# 7_Temp.net
KiCad netlist of a schematic drawn in Altium Designer
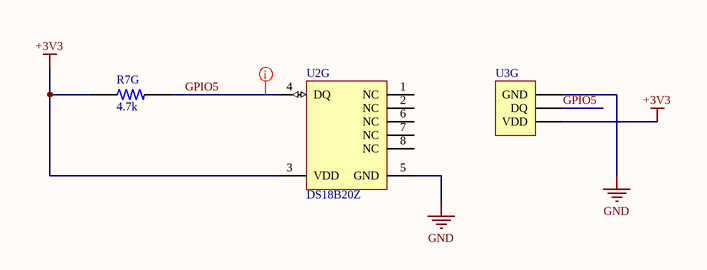
[diagram p0: 7_Temp.SchDoc]

(export (version "E")
  (design (tool "Eeschema 10.0.6"))
  (components
    (comp (ref "R7G")
      (value "4.7k")
      (footprint "R-0603")
      (description "0603")
      (fields (field (name "MP") "2-1623703-0") (field (name "TOLERANCE") "1%"))
      (libsource (lib "ESP-12F_WLED_IOT_LIPO") (part "R-0603"))
    )
    (comp (ref "U2G")
      (value "DS18B20Z")
      (footprint "MAXM-S8-2_N")
      (description "High-Precision 1-Wire Digital Thermometer, -55 to 125 degC, 8-Pin SOIC (S8-2)")
      (fields (field (name "GENERIC PART NUMBER") "DS18B20"))
      (libsource (lib "ESP-12F_WLED_IOT_LIPO") (part "DS18B20-S8-2"))
    )
    (comp (ref "U3G")
      (value "Header 3")
      (footprint "HDR1X3")
      (description "Header, 3-Pin")
      (fields (field (name "PUBLISHER") "Altium Limited"))
      (libsource (lib "ESP-12F_WLED_IOT_LIPO") (part "Header 3"))
    )
  )
  (nets
    (net (code "1") (name "+3V3") (class "Default")
      (node (ref "R7G") (pin "1") (pinfunction "1_1") (pintype "passive"))
      (node (ref "U2G") (pin "3") (pinfunction "VDD_3") (pintype "power_in"))
      (node (ref "U3G") (pin "3") (pinfunction "VDD_3") (pintype "passive"))
    )
    (net (code "2") (name "/GPIO5") (class "Default")
      (node (ref "R7G") (pin "2") (pinfunction "2_2") (pintype "passive"))
      (node (ref "U2G") (pin "4") (pinfunction "DQ_4") (pintype "bidirectional"))
      (node (ref "U3G") (pin "2") (pinfunction "DQ_2") (pintype "passive"))
    )
    (net (code "3") (name "GND") (class "Default")
      (node (ref "U2G") (pin "5") (pinfunction "GND_5") (pintype "power_in"))
      (node (ref "U3G") (pin "1") (pinfunction "GND_1") (pintype "passive"))
    )
    (net (code "4") (name "unconnected-(U2G-NC-Pad1)") (class "Default")
      (node (ref "U2G") (pin "1") (pinfunction "NC_1") (pintype "passive"))
    )
    (net (code "5") (name "unconnected-(U2G-NC-Pad2)") (class "Default")
      (node (ref "U2G") (pin "2") (pinfunction "NC_2") (pintype "passive"))
    )
    (net (code "6") (name "unconnected-(U2G-NC-Pad6)") (class "Default")
      (node (ref "U2G") (pin "6") (pinfunction "NC_6") (pintype "passive"))
    )
    (net (code "7") (name "unconnected-(U2G-NC-Pad7)") (class "Default")
      (node (ref "U2G") (pin "7") (pinfunction "NC_7") (pintype "passive"))
    )
    (net (code "8") (name "unconnected-(U2G-NC-Pad8)") (class "Default")
      (node (ref "U2G") (pin "8") (pinfunction "NC_8") (pintype "passive"))
    )
  )
)
